# 1_P1_schdoc.net
KiCad netlist of a schematic drawn in Altium Designer
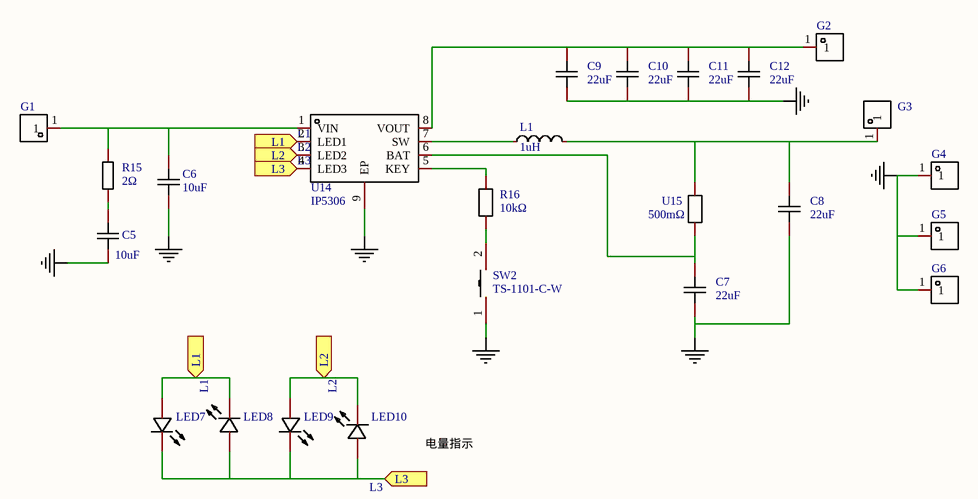
[diagram p0: 1_P1.schdoc.schdoc]

(export (version "E")
  (design (tool "Eeschema 10.0.6"))
  (components
    (comp (ref "C5")
      (value "10uF")
      (fields
        (field (name "NAME") "10uF")
        (field (name "MANUFACTURER") "muRata(村田)")
        (field (name "MANUFACTURER PART") "GRM21BR61H106KE43L")
        (field (name "TOLERANCE") "±10%")
      )
      (libsource (lib "altium-import") (part "root_3_GRM21BR61H106KE43L_"))
    )
    (comp (ref "C6")
      (value "10uF")
      (fields
        (field (name "NAME") "10uF")
        (field (name "MANUFACTURER") "muRata(村田)")
        (field (name "MANUFACTURER PART") "GRM21BR61H106KE43L")
        (field (name "TOLERANCE") "±10%")
      )
      (libsource (lib "altium-import") (part "root_1_GRM21BR61H106KE43L_"))
    )
    (comp (ref "C7")
      (value "22uF")
      (fields
        (field (name "NAME") "22uF")
        (field (name "MANUFACTURER") "SAMSUNG(三星)")
        (field (name "MANUFACTURER PART") "CL21A226MAYNNNE")
        (field (name "TOLERANCE") "±20%")
      )
      (libsource (lib "altium-import") (part "root_1_CL21A226MAYNNNE_"))
    )
    (comp (ref "C8")
      (value "22uF")
      (fields
        (field (name "NAME") "22uF")
        (field (name "MANUFACTURER") "SAMSUNG(三星)")
        (field (name "MANUFACTURER PART") "CL21A226MAYNNNE")
        (field (name "TOLERANCE") "±20%")
      )
      (libsource (lib "altium-import") (part "root_1_CL21A226MAYNNNE_"))
    )
    (comp (ref "C9")
      (value "22uF")
      (fields
        (field (name "NAME") "22uF")
        (field (name "MANUFACTURER") "SAMSUNG(三星)")
        (field (name "MANUFACTURER PART") "CL21A226MAYNNNE")
        (field (name "TOLERANCE") "±20%")
      )
      (libsource (lib "altium-import") (part "root_1_CL21A226MAYNNNE_"))
    )
    (comp (ref "C10")
      (value "22uF")
      (fields
        (field (name "NAME") "22uF")
        (field (name "MANUFACTURER") "SAMSUNG(三星)")
        (field (name "MANUFACTURER PART") "CL21A226MAYNNNE")
        (field (name "TOLERANCE") "±20%")
      )
      (libsource (lib "altium-import") (part "root_1_CL21A226MAYNNNE_"))
    )
    (comp (ref "C11")
      (value "22uF")
      (fields
        (field (name "NAME") "22uF")
        (field (name "MANUFACTURER") "SAMSUNG(三星)")
        (field (name "MANUFACTURER PART") "CL21A226MAYNNNE")
        (field (name "TOLERANCE") "±20%")
      )
      (libsource (lib "altium-import") (part "root_3_CL21A226MAYNNNE_"))
    )
    (comp (ref "C12")
      (value "22uF")
      (fields
        (field (name "NAME") "22uF")
        (field (name "MANUFACTURER") "SAMSUNG(三星)")
        (field (name "MANUFACTURER PART") "CL21A226MAYNNNE")
        (field (name "TOLERANCE") "±20%")
      )
      (libsource (lib "altium-import") (part "root_1_CL21A226MAYNNNE_"))
    )
    (comp (ref "G1") (value "封闭邮票焊盘") (libsource (lib "altium-import") (part "root_2_封闭邮票焊盘_")))
    (comp (ref "G2") (value "封闭邮票焊盘") (libsource (lib "altium-import") (part "root_0_封闭邮票焊盘_")))
    (comp (ref "G3") (value "封闭邮票焊盘") (libsource (lib "altium-import") (part "root_1_封闭邮票焊盘_")))
    (comp (ref "G4") (value "封闭邮票焊盘") (libsource (lib "altium-import") (part "root_0_封闭邮票焊盘_")))
    (comp (ref "G5") (value "封闭邮票焊盘") (libsource (lib "altium-import") (part "root_0_封闭邮票焊盘_")))
    (comp (ref "G6") (value "封闭邮票焊盘") (libsource (lib "altium-import") (part "root_0_封闭邮票焊盘_")))
    (comp (ref "L1")
      (value "1uH")
      (fields
        (field (name "NAME") "1uH")
        (field (name "MANUFACTURER") "cjiang(长江微电)")
        (field (name "MANUFACTURER PART") "FXL0420-1R0-M")
        (field (name "TOLERANCE") "±20%")
      )
      (libsource (lib "altium-import") (part "root_0_FXL0420-1R0-M_"))
    )
    (comp (ref "LED7")
      (value "NCD0805R1")
      (fields (field (name "MANUFACTURER") "国星光电"))
      (libsource (lib "altium-import") (part "root_1_mirrored_NCD0805R1_"))
    )
    (comp (ref "LED8")
      (value "NCD0805R1")
      (fields (field (name "MANUFACTURER") "国星光电"))
      (libsource (lib "altium-import") (part "root_3_mirrored_NCD0805R1_"))
    )
    (comp (ref "LED9")
      (value "NCD0805R1")
      (fields (field (name "MANUFACTURER") "国星光电"))
      (libsource (lib "altium-import") (part "root_1_mirrored_NCD0805R1_"))
    )
    (comp (ref "LED10")
      (value "NCD0805R1")
      (fields (field (name "MANUFACTURER") "国星光电"))
      (libsource (lib "altium-import") (part "root_3_mirrored_NCD0805R1_"))
    )
    (comp (ref "R15")
      (value "2Ω")
      (fields
        (field (name "NAME") "2Ω")
        (field (name "MANUFACTURER") "UNI-ROYAL(厚声)")
        (field (name "MANUFACTURER PART") "0805W8F200KT5E")
        (field (name "TOLERANCE") "±1%")
      )
      (libsource (lib "altium-import") (part "root_1_0805W8F200KT5E_"))
    )
    (comp (ref "R16")
      (value "10kΩ")
      (fields
        (field (name "NAME") "10kΩ")
        (field (name "MANUFACTURER") "FOJAN(富捷)")
        (field (name "MANUFACTURER PART") "FRC0805J103TS")
        (field (name "TOLERANCE") "±5%")
      )
      (libsource (lib "altium-import") (part "root_1_FRC0805J103TS_"))
    )
    (comp (ref "SW2")
      (value "TS-1101-C-W")
      (fields (field (name "NAME") "TS-1101-C-W") (field (name "MANUFACTURER") "XKB Connectivity(中国星坤)"))
      (libsource (lib "altium-import") (part "root_1_TS-1101-C-W_"))
    )
    (comp (ref "U14")
      (value "IP5306")
      (description "2.1A充电2.4A放电高集成度移动电源SOC")
      (fields (field (name "NAME") "IP5306") (field (name "MANUFACTURER") "INJOINIC(英集芯)"))
      (libsource (lib "altium-import") (part "root_0_IP5306_"))
    )
    (comp (ref "U15")
      (value "500mΩ")
      (fields
        (field (name "NAME") "500mΩ")
        (field (name "MANUFACTURER") "FOJAN(富捷)")
        (field (name "MANUFACTURER PART") "FRL0805JR500TS")
        (field (name "TOLERANCE") "±5%")
      )
      (libsource (lib "altium-import") (part "root_1_FRL0805JR500TS_"))
    )
  )
  (nets
    (net (code "1") (name "/L1") (class "Default")
      (node (ref "LED7") (pin "1") (pinfunction "+_1") (pintype "passive"))
      (node (ref "LED8") (pin "2") (pinfunction "-_2") (pintype "passive"))
      (node (ref "U14") (pin "2") (pinfunction "LED1_2") (pintype "passive"))
    )
    (net (code "2") (name "/L2") (class "Default")
      (node (ref "LED10") (pin "2") (pinfunction "-_2") (pintype "passive"))
      (node (ref "LED9") (pin "1") (pinfunction "+_1") (pintype "passive"))
      (node (ref "U14") (pin "3") (pinfunction "LED2_3") (pintype "passive"))
    )
    (net (code "3") (name "/L3") (class "Default")
      (node (ref "LED10") (pin "1") (pinfunction "+_1") (pintype "passive"))
      (node (ref "LED7") (pin "2") (pinfunction "-_2") (pintype "passive"))
      (node (ref "LED8") (pin "1") (pinfunction "+_1") (pintype "passive"))
      (node (ref "LED9") (pin "2") (pinfunction "-_2") (pintype "passive"))
      (node (ref "U14") (pin "4") (pinfunction "LED3_4") (pintype "passive"))
    )
    (net (code "4") (name "<NO NET>") (class "Default")
      (node (ref "C10") (pin "1") (pinfunction "1_1") (pintype "passive"))
      (node (ref "C11") (pin "2") (pinfunction "2_2") (pintype "passive"))
      (node (ref "C12") (pin "1") (pinfunction "1_1") (pintype "passive"))
      (node (ref "C5") (pin "2") (pinfunction "2_2") (pintype "passive"))
      (node (ref "C6") (pin "1") (pinfunction "1_1") (pintype "passive"))
      (node (ref "C7") (pin "1") (pinfunction "1_1") (pintype "passive"))
      (node (ref "C8") (pin "1") (pinfunction "1_1") (pintype "passive"))
      (node (ref "C9") (pin "1") (pinfunction "1_1") (pintype "passive"))
      (node (ref "G4") (pin "1") (pinfunction "1_1") (pintype "passive"))
      (node (ref "G5") (pin "1") (pinfunction "1_1") (pintype "passive"))
      (node (ref "G6") (pin "1") (pinfunction "1_1") (pintype "passive"))
      (node (ref "SW2") (pin "1") (pinfunction "1_1") (pintype "passive"))
      (node (ref "U14") (pin "9") (pinfunction "EP_9") (pintype "passive"))
    )
    (net (code "5") (name "Net-(C5-Pad1)") (class "Default")
      (node (ref "C5") (pin "1") (pinfunction "1_1") (pintype "passive"))
      (node (ref "R15") (pin "1") (pinfunction "1_1") (pintype "passive"))
    )
    (net (code "6") (name "Net-(C8-Pad2)") (class "Default")
      (node (ref "C8") (pin "2") (pinfunction "2_2") (pintype "passive"))
      (node (ref "G3") (pin "1") (pinfunction "1_1") (pintype "passive"))
      (node (ref "L1") (pin "2") (pinfunction "2_2") (pintype "passive"))
      (node (ref "U15") (pin "2") (pinfunction "2_2") (pintype "passive"))
    )
    (net (code "7") (name "Net-(R16-Pad1)") (class "Default")
      (node (ref "R16") (pin "1") (pinfunction "1_1") (pintype "passive"))
      (node (ref "SW2") (pin "2") (pinfunction "2_2") (pintype "passive"))
    )
    (net (code "8") (name "Net-(U14-BAT)") (class "Default")
      (node (ref "C7") (pin "2") (pinfunction "2_2") (pintype "passive"))
      (node (ref "U14") (pin "6") (pinfunction "BAT_6") (pintype "passive"))
      (node (ref "U15") (pin "1") (pinfunction "1_1") (pintype "passive"))
    )
    (net (code "9") (name "Net-(U14-KEY)") (class "Default")
      (node (ref "R16") (pin "2") (pinfunction "2_2") (pintype "passive"))
      (node (ref "U14") (pin "5") (pinfunction "KEY_5") (pintype "passive"))
    )
    (net (code "10") (name "Net-(U14-SW)") (class "Default")
      (node (ref "L1") (pin "1") (pinfunction "1_1") (pintype "passive"))
      (node (ref "U14") (pin "7") (pinfunction "SW_7") (pintype "passive"))
    )
    (net (code "11") (name "Net-(U14-VIN)") (class "Default")
      (node (ref "C6") (pin "2") (pinfunction "2_2") (pintype "passive"))
      (node (ref "G1") (pin "1") (pinfunction "1_1") (pintype "passive"))
      (node (ref "R15") (pin "2") (pinfunction "2_2") (pintype "passive"))
      (node (ref "U14") (pin "1") (pinfunction "VIN_1") (pintype "passive"))
    )
    (net (code "12") (name "Net-(U14-VOUT)") (class "Default")
      (node (ref "C10") (pin "2") (pinfunction "2_2") (pintype "passive"))
      (node (ref "C11") (pin "1") (pinfunction "1_1") (pintype "passive"))
      (node (ref "C12") (pin "2") (pinfunction "2_2") (pintype "passive"))
      (node (ref "C9") (pin "2") (pinfunction "2_2") (pintype "passive"))
      (node (ref "G2") (pin "1") (pinfunction "1_1") (pintype "passive"))
      (node (ref "U14") (pin "8") (pinfunction "VOUT_8") (pintype "passive"))
    )
  )
)
